# WiicameraSingleV2.net
KiCad netlist of a schematic drawn in EAGLE
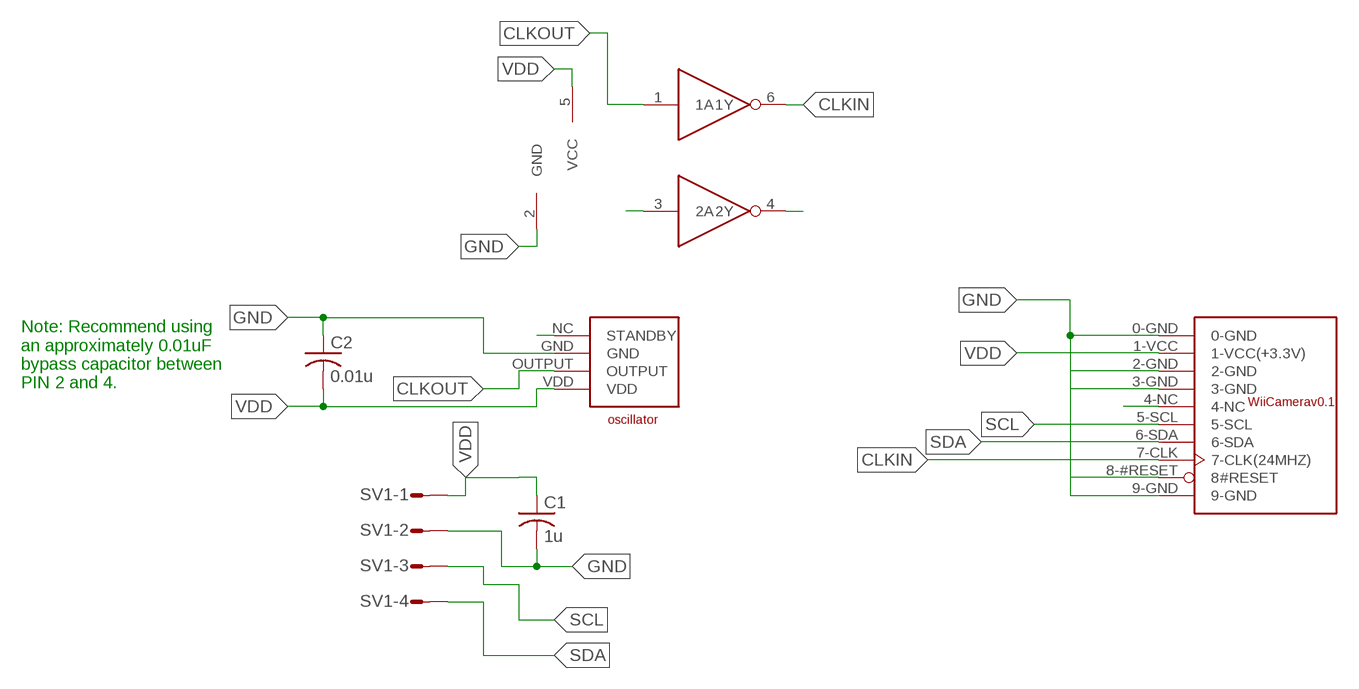
[diagram p0: schematic, sheet 1]

(export (version "E")
  (design (tool "Eeschema 10.0.6"))
  (components
    (comp (ref "C1")
      (value "1u")
      (footprint "eagle-import:C0805")
      (libsource (lib "eagle-import") (part "C-USC0805"))
    )
    (comp (ref "C2")
      (value "0.01u")
      (footprint "eagle-import:C0805")
      (libsource (lib "eagle-import") (part "C-USC0805"))
    )
    (comp (ref "DUALINV1")
      (value "SN74LVC2G04")
      (footprint "eagle-import:SN74LVC2G04")
      (libsource (lib "eagle-import") (part "SN74LVC2G04"))
    )
    (comp (ref "OSC1")
      (value "OSCILLATOR4-SMD")
      (footprint "eagle-import:OSCILLATOR4-SMD")
      (libsource (lib "eagle-import") (part "OSCILLATOR4-SMD"))
    )
    (comp (ref "SV1")
      (value "S04P")
      (footprint "eagle-import:S04P")
      (libsource (lib "eagle-import") (part "S04P"))
    )
    (comp (ref "WII1")
      (value "WIICAMERA")
      (footprint "eagle-import:WIICAMERA")
      (libsource (lib "eagle-import") (part "WIICAMERA"))
    )
  )
  (nets
    (net (code "1") (name "CLKIN") (class "Default")
      (node (ref "DUALINV1") (pin "6") (pinfunction "1Y_6") (pintype "output"))
      (node (ref "WII1") (pin "7-CLK") (pinfunction "7-CLK(24MHZ)_7-CLK") (pintype "open_collector"))
    )
    (net (code "2") (name "CLKOUT") (class "Default")
      (node (ref "DUALINV1") (pin "1") (pinfunction "1A_1") (pintype "input"))
      (node (ref "OSC1") (pin "OUTPUT") (pinfunction "OUTPUT_OUTPUT") (pintype "open_collector"))
    )
    (net (code "3") (name "GND") (class "Default")
      (node (ref "C1") (pin "2") (pinfunction "2_2") (pintype "passive"))
      (node (ref "C2") (pin "1") (pinfunction "1_1") (pintype "passive"))
      (node (ref "DUALINV1") (pin "2") (pinfunction "GND_2") (pintype "bidirectional"))
      (node (ref "OSC1") (pin "GND") (pinfunction "GND_GND") (pintype "power_in"))
      (node (ref "SV1") (pin "2") (pinfunction "S_2") (pintype "passive"))
      (node (ref "WII1") (pin "0-GND") (pinfunction "0-GND_0-GND") (pintype "power_in"))
      (node (ref "WII1") (pin "2-GND") (pinfunction "2-GND_2-GND") (pintype "power_in"))
      (node (ref "WII1") (pin "3-GND") (pinfunction "3-GND_3-GND") (pintype "power_in"))
      (node (ref "WII1") (pin "8-#RESET") (pinfunction "8#RESET_8-#RESET") (pintype "input"))
      (node (ref "WII1") (pin "9-GND") (pinfunction "9-GND_9-GND") (pintype "power_in"))
    )
    (net (code "4") (name "SCL") (class "Default")
      (node (ref "SV1") (pin "3") (pinfunction "S_3") (pintype "passive"))
      (node (ref "WII1") (pin "5-SCL") (pinfunction "5-SCL_5-SCL") (pintype "bidirectional"))
    )
    (net (code "5") (name "SDA") (class "Default")
      (node (ref "SV1") (pin "4") (pinfunction "S_4") (pintype "passive"))
      (node (ref "WII1") (pin "6-SDA") (pinfunction "6-SDA_6-SDA") (pintype "bidirectional"))
    )
    (net (code "6") (name "VDD") (class "Default")
      (node (ref "C1") (pin "1") (pinfunction "1_1") (pintype "passive"))
      (node (ref "C2") (pin "2") (pinfunction "2_2") (pintype "passive"))
      (node (ref "DUALINV1") (pin "5") (pinfunction "VCC_5") (pintype "bidirectional"))
      (node (ref "OSC1") (pin "VDD") (pinfunction "VDD_VDD") (pintype "power_in"))
      (node (ref "SV1") (pin "1") (pinfunction "S_1") (pintype "passive"))
      (node (ref "WII1") (pin "1-VCC") (pinfunction "1-VCC(+3.3V)_1-VCC") (pintype "power_in"))
    )
    (net (code "7") (name "unconnected-(DUALINV1-2A-Pad3)") (class "Default")
      (node (ref "DUALINV1") (pin "3") (pinfunction "2A_3") (pintype "input"))
    )
    (net (code "8") (name "unconnected-(DUALINV1-2Y-Pad4)") (class "Default")
      (node (ref "DUALINV1") (pin "4") (pinfunction "2Y_4") (pintype "output"))
    )
    (net (code "9") (name "unconnected-(OSC1-STANDBY-PadNC)") (class "Default")
      (node (ref "OSC1") (pin "NC") (pinfunction "STANDBY_NC") (pintype "no_connect"))
    )
    (net (code "10") (name "unconnected-(WII1-Pad4-NC)") (class "Default")
      (node (ref "WII1") (pin "4-NC") (pinfunction "4-NC_4-NC") (pintype "no_connect"))
    )
  )
)
